# SCH_V1_0.net
KiCad netlist of a schematic drawn in Altium Designer
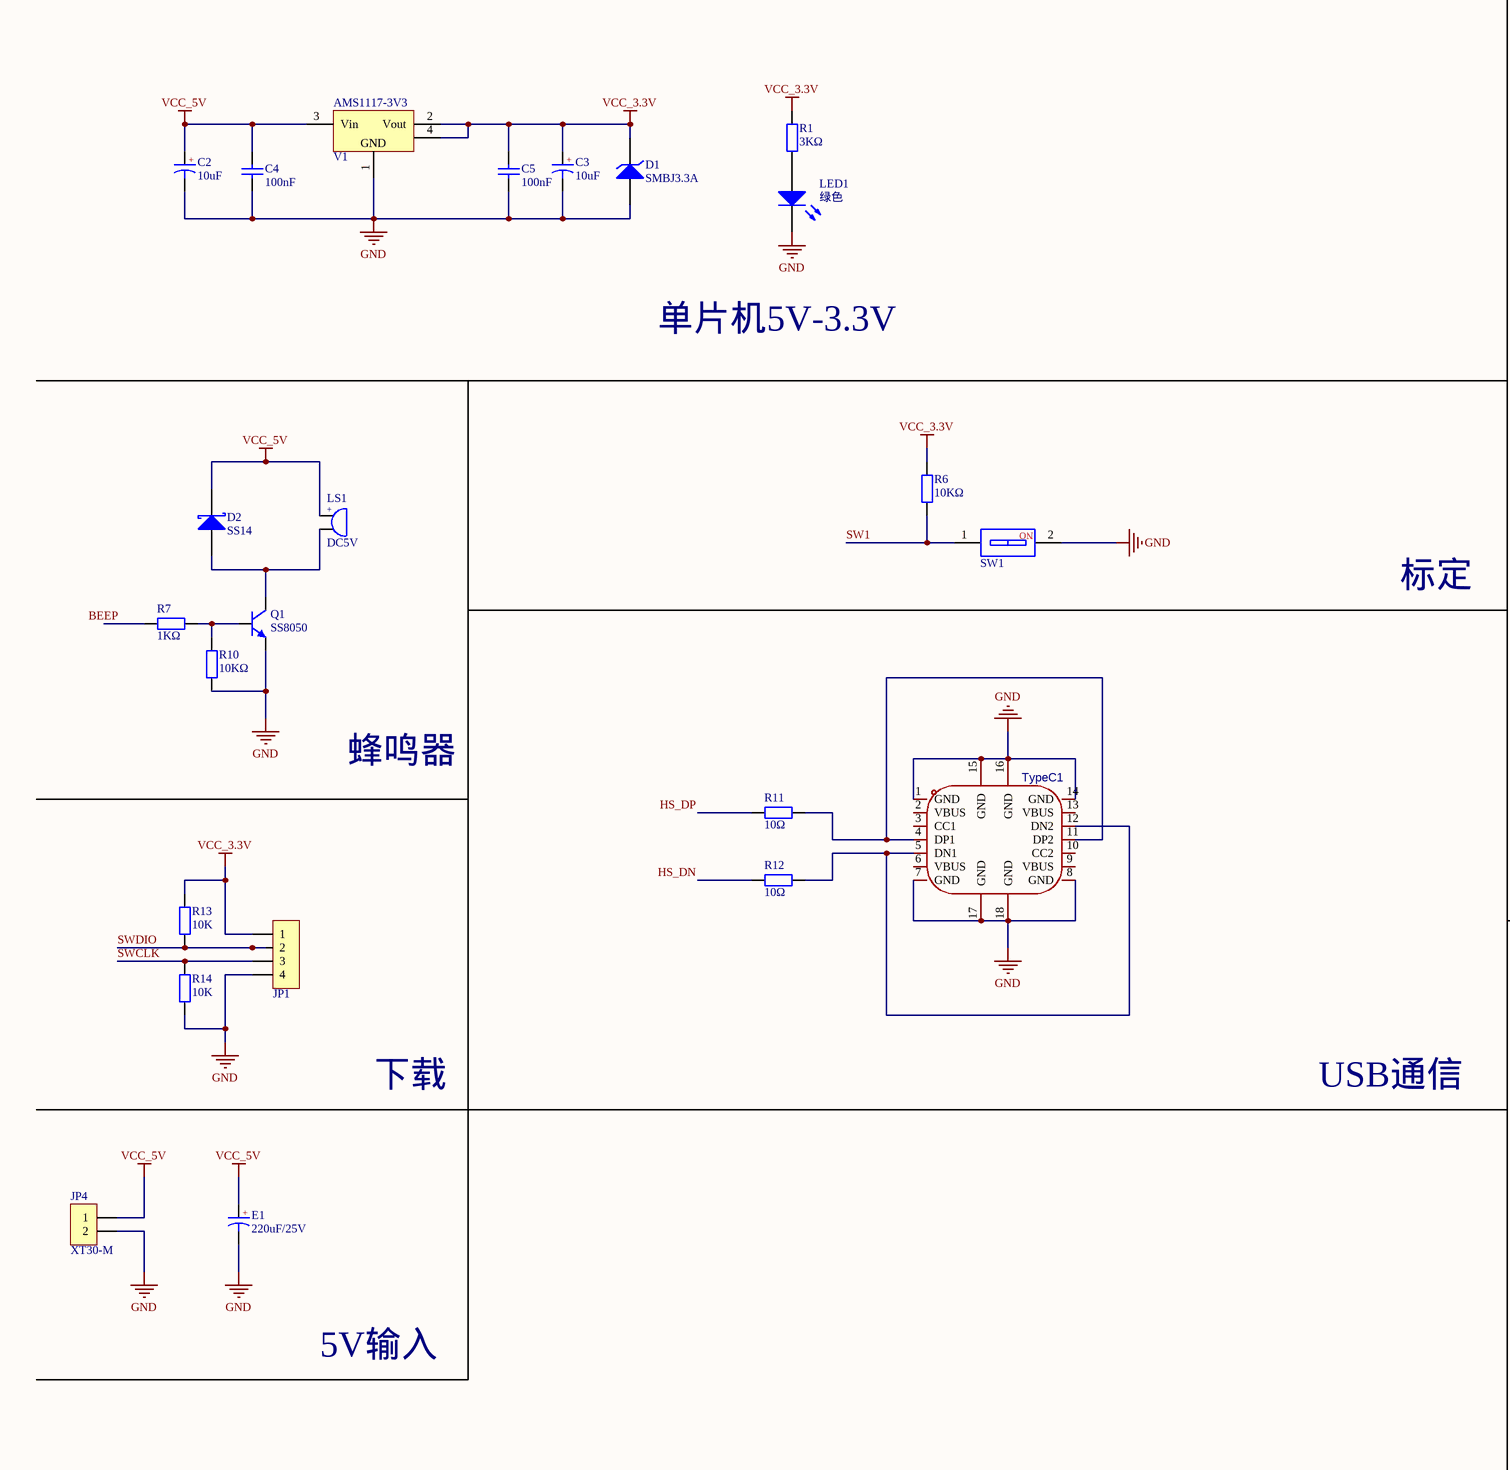
[diagram p0: SCH_V1.0.SchDoc, left]
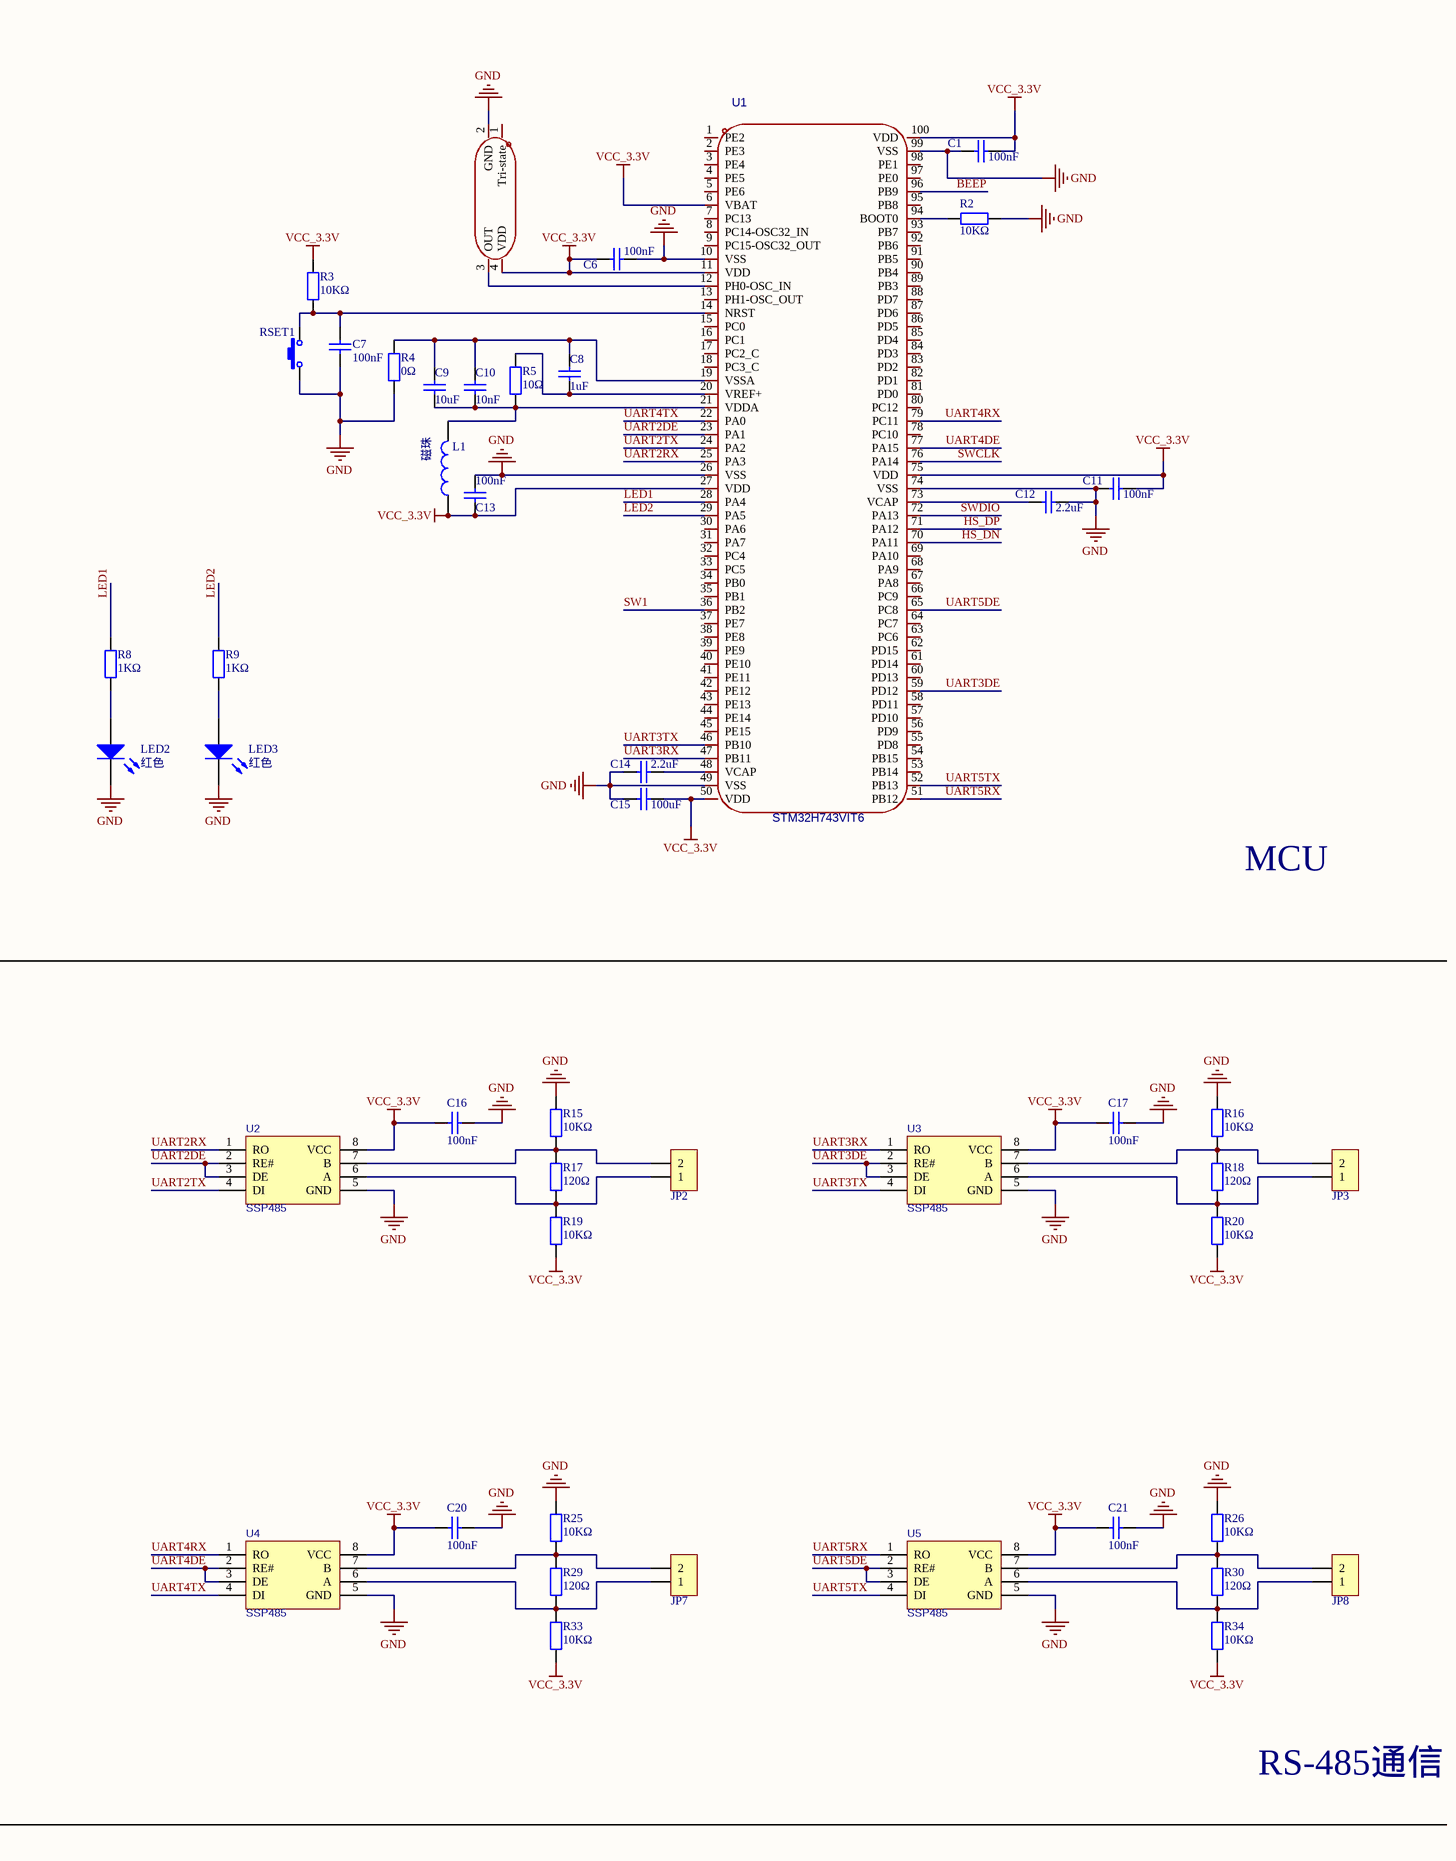
[diagram p1: SCH_V1.0.SchDoc, right]

(export (version "E")
  (design (tool "Eeschema 10.0.6"))
  (components
    (comp (ref "C1")
      (value "100nF")
      (footprint "C0603_L")
      (description "贴片电容/MLCC电容")
      (libsource (lib "0.1 - 电阻-电容-电感-保险丝-晶振-晶体-磁珠-电位器-法拉电容-馈通电容") (part "C"))
    )
    (comp (ref "C2")
      (value "10uF")
      (footprint "C_3216")
      (description "贴片钽电容")
      (libsource (lib "0.1 - 电阻-电容-电感-保险丝-晶振-晶体-磁珠-电位器-法拉电容-馈通电容") (part "CT"))
    )
    (comp (ref "C3")
      (value "10uF")
      (footprint "C_3216")
      (description "贴片钽电容")
      (libsource (lib "0.1 - 电阻-电容-电感-保险丝-晶振-晶体-磁珠-电位器-法拉电容-馈通电容") (part "CT"))
    )
    (comp (ref "C4")
      (value "100nF")
      (footprint "C1206_L")
      (description "贴片电容/MLCC电容")
      (libsource (lib "0.1 - 电阻-电容-电感-保险丝-晶振-晶体-磁珠-电位器-法拉电容-馈通电容") (part "C"))
    )
    (comp (ref "C5")
      (value "100nF")
      (footprint "C1206_L")
      (description "贴片电容/MLCC电容")
      (libsource (lib "0.1 - 电阻-电容-电感-保险丝-晶振-晶体-磁珠-电位器-法拉电容-馈通电容") (part "C"))
    )
    (comp (ref "C6")
      (value "100nF")
      (footprint "C0603_L")
      (description "贴片电容/MLCC电容")
      (libsource (lib "0.1 - 电阻-电容-电感-保险丝-晶振-晶体-磁珠-电位器-法拉电容-馈通电容") (part "C"))
    )
    (comp (ref "C7")
      (value "100nF")
      (footprint "C0603_L")
      (description "贴片电容/MLCC电容")
      (libsource (lib "0.1 - 电阻-电容-电感-保险丝-晶振-晶体-磁珠-电位器-法拉电容-馈通电容") (part "C"))
    )
    (comp (ref "C8")
      (value "1uF")
      (footprint "C0603_L")
      (description "贴片电容/MLCC电容")
      (libsource (lib "0.1 - 电阻-电容-电感-保险丝-晶振-晶体-磁珠-电位器-法拉电容-馈通电容") (part "C"))
    )
    (comp (ref "C9")
      (value "10uF")
      (footprint "C0603_L")
      (description "贴片电容/MLCC电容")
      (libsource (lib "0.1 - 电阻-电容-电感-保险丝-晶振-晶体-磁珠-电位器-法拉电容-馈通电容") (part "C"))
    )
    (comp (ref "C10")
      (value "10nF")
      (footprint "C0603_L")
      (description "贴片电容/MLCC电容")
      (libsource (lib "0.1 - 电阻-电容-电感-保险丝-晶振-晶体-磁珠-电位器-法拉电容-馈通电容") (part "C"))
    )
    (comp (ref "C11")
      (value "100nF")
      (footprint "C0603_L")
      (description "贴片电容/MLCC电容")
      (libsource (lib "0.1 - 电阻-电容-电感-保险丝-晶振-晶体-磁珠-电位器-法拉电容-馈通电容") (part "C"))
    )
    (comp (ref "C12")
      (value "2.2uF")
      (footprint "C0603_L")
      (description "贴片电容/MLCC电容")
      (libsource (lib "0.1 - 电阻-电容-电感-保险丝-晶振-晶体-磁珠-电位器-法拉电容-馈通电容") (part "C"))
    )
    (comp (ref "C13")
      (value "100nF")
      (footprint "C0603_L")
      (description "贴片电容/MLCC电容")
      (libsource (lib "0.1 - 电阻-电容-电感-保险丝-晶振-晶体-磁珠-电位器-法拉电容-馈通电容") (part "C"))
    )
    (comp (ref "C14")
      (value "2.2uF")
      (footprint "C0603_L")
      (description "贴片电容/MLCC电容")
      (libsource (lib "0.1 - 电阻-电容-电感-保险丝-晶振-晶体-磁珠-电位器-法拉电容-馈通电容") (part "C"))
    )
    (comp (ref "C15")
      (value "100uF")
      (footprint "C0603_L")
      (description "贴片电容/MLCC电容")
      (libsource (lib "0.1 - 电阻-电容-电感-保险丝-晶振-晶体-磁珠-电位器-法拉电容-馈通电容") (part "C"))
    )
    (comp (ref "C16")
      (value "100nF")
      (footprint "C0603_L")
      (description "瓷片电容")
      (libsource (lib "0.1 - 电阻-电容-电感-保险丝-晶振-晶体-磁珠-电位器-法拉电容-馈通电容") (part "CC"))
    )
    (comp (ref "C17")
      (value "100nF")
      (footprint "C0603_L")
      (description "瓷片电容")
      (libsource (lib "0.1 - 电阻-电容-电感-保险丝-晶振-晶体-磁珠-电位器-法拉电容-馈通电容") (part "CC"))
    )
    (comp (ref "C20")
      (value "100nF")
      (footprint "C0603_L")
      (description "瓷片电容")
      (libsource (lib "0.1 - 电阻-电容-电感-保险丝-晶振-晶体-磁珠-电位器-法拉电容-馈通电容") (part "CC"))
    )
    (comp (ref "C21")
      (value "100nF")
      (footprint "C0603_L")
      (description "瓷片电容")
      (libsource (lib "0.1 - 电阻-电容-电感-保险丝-晶振-晶体-磁珠-电位器-法拉电容-馈通电容") (part "CC"))
    )
    (comp (ref "D1")
      (value "SMBJ3.3A")
      (footprint "SMB")
      (description "30V 600W瞬态抑制二极管")
      (libsource (lib "0.2 - 二极管-TVS-ESD-整流桥-放电管") (part "SMBJ30A-E3/52"))
    )
    (comp (ref "D2")
      (value "SS14")
      (footprint "SMA")
      (description "肖特基二极管")
      (libsource (lib "0.2 - 二极管-TVS-ESD-整流桥-放电管") (part "SS14"))
    )
    (comp (ref "E1")
      (value "220uF/25V")
      (footprint "CS 6*6 - B")
      (description "贴片固态电容")
      (libsource (lib "0.1 - 电阻-电容-电感-保险丝-晶振-晶体-磁珠-电位器-法拉电容-馈通电容") (part "CS_SMD"))
    )
    (comp (ref "JP1")
      (value "HDR-1X4")
      (footprint "XH2.54-W-4P")
      (description "4P接插件")
      (libsource (lib "5.5 - 2.54mm连接器(KF2EDGK_XH2.54_2.54排针排母)") (part "Header 4"))
    )
    (comp (ref "JP2")
      (value "HDR-1X2")
      (footprint "XH2.54-W-2P")
      (description "2P接插件")
      (libsource (lib "5.5 - 2.54mm连接器(KF2EDGK_XH2.54_2.54排针排母)") (part "Header 2"))
    )
    (comp (ref "JP3")
      (value "HDR-1X2")
      (footprint "XH2.54-W-2P")
      (description "2P接插件")
      (libsource (lib "5.5 - 2.54mm连接器(KF2EDGK_XH2.54_2.54排针排母)") (part "Header 2"))
    )
    (comp (ref "JP4")
      (value "XT30-M")
      (footprint "XT30PW-M")
      (description "XT30公头")
      (libsource (lib "0.6 - 电源_音频_USB Type-C_HDMI_XT60_5557_D-SUB_RJ45_SD-TF_SIM插座") (part "XT30-M"))
    )
    (comp (ref "JP7")
      (value "HDR-1X2")
      (footprint "XH2.54-W-2P")
      (description "2P接插件")
      (libsource (lib "5.5 - 2.54mm连接器(KF2EDGK_XH2.54_2.54排针排母)") (part "Header 2"))
    )
    (comp (ref "JP8")
      (value "HDR-1X2")
      (footprint "XH2.54-W-2P")
      (description "2P接插件")
      (libsource (lib "5.5 - 2.54mm连接器(KF2EDGK_XH2.54_2.54排针排母)") (part "Header 2"))
    )
    (comp (ref "L1")
      (value "磁珠")
      (footprint "L0603")
      (description "贴片小功率电感")
      (libsource (lib "0.1 - 电阻-电容-电感-保险丝-晶振-晶体-磁珠-电位器-法拉电容-馈通电容") (part "L"))
    )
    (comp (ref "LED1")
      (value "绿色")
      (footprint "LED0603_B")
      (description "贴片LED")
      (libsource (lib "0.3 - LED发光二极管-IR二极管_接收管-光耦") (part "LED"))
    )
    (comp (ref "LED2")
      (value "红色")
      (footprint "LED0603_G")
      (description "贴片LED")
      (libsource (lib "0.3 - LED发光二极管-IR二极管_接收管-光耦") (part "LED"))
    )
    (comp (ref "LED3")
      (value "红色")
      (footprint "LED0603_R")
      (description "贴片LED")
      (libsource (lib "0.3 - LED发光二极管-IR二极管_接收管-光耦") (part "LED"))
    )
    (comp (ref "LS1")
      (value "DC5V")
      (footprint "BEEP 5x9x5.5")
      (description "蜂鸣器")
      (libsource (lib "0.5 - 按键_开关_蜂鸣器_电池_测试点_Mark点_铜柱") (part "BEEP"))
    )
    (comp (ref "OSC1")
      (value "8MHz")
      (footprint "XTAL-3225-4P")
      (fields
        (field (name "MANUFACTURER") "YXC(扬兴晶振)")
        (field (name "MANUFACTURER PART") "OT2EL4C4JI-111OLP-8M")
      )
      (libsource (lib "0.1 - 电阻-电容-电感-保险丝-晶振-晶体-磁珠-电位器-法拉电容-馈通电容") (part "XTAL-OT2EL4C4JI"))
    )
    (comp (ref "Q1")
      (value "SS8050")
      (footprint "SOT23-3N")
      (description "高频放大-NPN型")
      (libsource (lib "0.4 - 三极管-场效应管-可控硅") (part "8050-SMD"))
    )
    (comp (ref "R1")
      (value "3KΩ")
      (footprint "R0603_L")
      (description "贴片电阻")
      (libsource (lib "0.1 - 电阻-电容-电感-保险丝-晶振-晶体-磁珠-电位器-法拉电容-馈通电容") (part "R"))
    )
    (comp (ref "R2")
      (value "10KΩ")
      (footprint "R0603_L")
      (description "贴片电阻")
      (libsource (lib "0.1 - 电阻-电容-电感-保险丝-晶振-晶体-磁珠-电位器-法拉电容-馈通电容") (part "R"))
    )
    (comp (ref "R3")
      (value "10KΩ")
      (footprint "R0603_L")
      (description "贴片电阻")
      (libsource (lib "0.1 - 电阻-电容-电感-保险丝-晶振-晶体-磁珠-电位器-法拉电容-馈通电容") (part "R"))
    )
    (comp (ref "R4")
      (value "0Ω")
      (footprint "R0603_L")
      (description "贴片电阻")
      (libsource (lib "0.1 - 电阻-电容-电感-保险丝-晶振-晶体-磁珠-电位器-法拉电容-馈通电容") (part "R"))
    )
    (comp (ref "R5")
      (value "10Ω")
      (footprint "R0603_L")
      (description "贴片电阻")
      (libsource (lib "0.1 - 电阻-电容-电感-保险丝-晶振-晶体-磁珠-电位器-法拉电容-馈通电容") (part "R"))
    )
    (comp (ref "R6")
      (value "10KΩ")
      (footprint "R0603_L")
      (description "贴片电阻")
      (libsource (lib "0.1 - 电阻-电容-电感-保险丝-晶振-晶体-磁珠-电位器-法拉电容-馈通电容") (part "R"))
    )
    (comp (ref "R7")
      (value "1KΩ")
      (footprint "R0603_L")
      (description "贴片电阻")
      (libsource (lib "0.1 - 电阻-电容-电感-保险丝-晶振-晶体-磁珠-电位器-法拉电容-馈通电容") (part "R"))
    )
    (comp (ref "R8")
      (value "1KΩ")
      (footprint "R0603_L")
      (description "贴片电阻")
      (libsource (lib "0.1 - 电阻-电容-电感-保险丝-晶振-晶体-磁珠-电位器-法拉电容-馈通电容") (part "R"))
    )
    (comp (ref "R9")
      (value "1KΩ")
      (footprint "R0603_L")
      (description "贴片电阻")
      (libsource (lib "0.1 - 电阻-电容-电感-保险丝-晶振-晶体-磁珠-电位器-法拉电容-馈通电容") (part "R"))
    )
    (comp (ref "R10")
      (value "10KΩ")
      (footprint "R0603_L")
      (description "贴片电阻")
      (libsource (lib "0.1 - 电阻-电容-电感-保险丝-晶振-晶体-磁珠-电位器-法拉电容-馈通电容") (part "R"))
    )
    (comp (ref "R11")
      (value "10Ω")
      (footprint "R0603_L")
      (description "贴片电阻")
      (libsource (lib "0.1 - 电阻-电容-电感-保险丝-晶振-晶体-磁珠-电位器-法拉电容-馈通电容") (part "R"))
    )
    (comp (ref "R12")
      (value "10Ω")
      (footprint "R0603_L")
      (description "贴片电阻")
      (libsource (lib "0.1 - 电阻-电容-电感-保险丝-晶振-晶体-磁珠-电位器-法拉电容-馈通电容") (part "R"))
    )
    (comp (ref "R13")
      (value "10K")
      (footprint "R0603_L")
      (description "贴片电阻")
      (libsource (lib "0.1 - 电阻-电容-电感-保险丝-晶振-晶体-磁珠-电位器-法拉电容-馈通电容") (part "R"))
    )
    (comp (ref "R14")
      (value "10K")
      (footprint "R0603_L")
      (description "贴片电阻")
      (libsource (lib "0.1 - 电阻-电容-电感-保险丝-晶振-晶体-磁珠-电位器-法拉电容-馈通电容") (part "R"))
    )
    (comp (ref "R15")
      (value "10KΩ")
      (footprint "R0603_L")
      (description "贴片电阻")
      (libsource (lib "0.1 - 电阻-电容-电感-保险丝-晶振-晶体-磁珠-电位器-法拉电容-馈通电容") (part "R"))
    )
    (comp (ref "R16")
      (value "10KΩ")
      (footprint "R0603_L")
      (description "贴片电阻")
      (libsource (lib "0.1 - 电阻-电容-电感-保险丝-晶振-晶体-磁珠-电位器-法拉电容-馈通电容") (part "R"))
    )
    (comp (ref "R17")
      (value "120Ω")
      (footprint "R0603_L")
      (description "贴片电阻")
      (libsource (lib "0.1 - 电阻-电容-电感-保险丝-晶振-晶体-磁珠-电位器-法拉电容-馈通电容") (part "R"))
    )
    (comp (ref "R18")
      (value "120Ω")
      (footprint "R0603_L")
      (description "贴片电阻")
      (libsource (lib "0.1 - 电阻-电容-电感-保险丝-晶振-晶体-磁珠-电位器-法拉电容-馈通电容") (part "R"))
    )
    (comp (ref "R19")
      (value "10KΩ")
      (footprint "R0603_L")
      (description "贴片电阻")
      (libsource (lib "0.1 - 电阻-电容-电感-保险丝-晶振-晶体-磁珠-电位器-法拉电容-馈通电容") (part "R"))
    )
    (comp (ref "R20")
      (value "10KΩ")
      (footprint "R0603_L")
      (description "贴片电阻")
      (libsource (lib "0.1 - 电阻-电容-电感-保险丝-晶振-晶体-磁珠-电位器-法拉电容-馈通电容") (part "R"))
    )
    (comp (ref "R25")
      (value "10KΩ")
      (footprint "R0603_L")
      (description "贴片电阻")
      (libsource (lib "0.1 - 电阻-电容-电感-保险丝-晶振-晶体-磁珠-电位器-法拉电容-馈通电容") (part "R"))
    )
    (comp (ref "R26")
      (value "10KΩ")
      (footprint "R0603_L")
      (description "贴片电阻")
      (libsource (lib "0.1 - 电阻-电容-电感-保险丝-晶振-晶体-磁珠-电位器-法拉电容-馈通电容") (part "R"))
    )
    (comp (ref "R29")
      (value "120Ω")
      (footprint "R0603_L")
      (description "贴片电阻")
      (libsource (lib "0.1 - 电阻-电容-电感-保险丝-晶振-晶体-磁珠-电位器-法拉电容-馈通电容") (part "R"))
    )
    (comp (ref "R30")
      (value "120Ω")
      (footprint "R0603_L")
      (description "贴片电阻")
      (libsource (lib "0.1 - 电阻-电容-电感-保险丝-晶振-晶体-磁珠-电位器-法拉电容-馈通电容") (part "R"))
    )
    (comp (ref "R33")
      (value "10KΩ")
      (footprint "R0603_L")
      (description "贴片电阻")
      (libsource (lib "0.1 - 电阻-电容-电感-保险丝-晶振-晶体-磁珠-电位器-法拉电容-馈通电容") (part "R"))
    )
    (comp (ref "R34")
      (value "10KΩ")
      (footprint "R0603_L")
      (description "贴片电阻")
      (libsource (lib "0.1 - 电阻-电容-电感-保险丝-晶振-晶体-磁珠-电位器-法拉电容-馈通电容") (part "R"))
    )
    (comp (ref "RSET1")
      (value "3x6x5")
      (footprint "SW SMD-3*6*2.5")
      (description "微动开关")
      (libsource (lib "0.5 - 按键_开关_蜂鸣器_电池_测试点_Mark点_铜柱") (part "SW-PB"))
    )
    (comp (ref "SW1")
      (value "DIP-SW-1P")
      (footprint "SW DIP-1P")
      (description "1路拨码开关")
      (libsource (lib "0.5 - 按键_开关_蜂鸣器_电池_测试点_Mark点_铜柱") (part "DIP-SW-1P"))
    )
    (comp (ref "TypeC1")
      (value "U264-141N-4BAC10")
      (footprint "USB-C-Type-侧插")
      (fields (field (name "MANUFACTURER") "XKB Connectivity(中国星坤)"))
      (libsource (lib "0.6 - 电源_音频_USB Type-C_HDMI_XT60_5557_D-SUB_RJ45_SD-TF_SIM插座") (part "USB3.0-Type-C-侧插"))
    )
    (comp (ref "U1")
      (value "STM32H743VIT6")
      (footprint "LQFP-100_L14.0-W14.0-P0.50-LS16.0-BL")
      (fields (field (name "MANUFACTURER") "ST(意法半导体)"))
      (libsource (lib "2.8 - STM32 F7-H7-MP系列单片机") (part "STM32H743VIT6_C114409"))
    )
    (comp (ref "U2")
      (value "SSP485")
      (footprint "SOP-8")
      (description "RS485/RS422收发器芯片")
      (libsource (lib "0.8 - 常见芯片") (part "MAX3485CSA"))
    )
    (comp (ref "U3")
      (value "SSP485")
      (footprint "SOP-8")
      (description "RS485/RS422收发器芯片")
      (libsource (lib "0.8 - 常见芯片") (part "MAX3485CSA"))
    )
    (comp (ref "U4")
      (value "SSP485")
      (footprint "SOP-8")
      (description "RS485/RS422收发器芯片")
      (libsource (lib "0.8 - 常见芯片") (part "MAX3485CSA"))
    )
    (comp (ref "U5")
      (value "SSP485")
      (footprint "SOP-8")
      (description "RS485/RS422收发器芯片")
      (libsource (lib "0.8 - 常见芯片") (part "MAX3485CSA"))
    )
    (comp (ref "V1")
      (value "AMS1117-3V3")
      (footprint "SOT223_L")
      (description "三端稳压芯片")
      (libsource (lib "0.7 - 电源类芯片") (part "AMS1117"))
    )
  )
  (nets
    (net (code "1") (name "/BEEP") (class "Default")
      (node (ref "R7") (pin "1") (pinfunction "1_1") (pintype "passive"))
      (node (ref "U1") (pin "96") (pinfunction "PB9_96") (pintype "passive"))
    )
    (net (code "2") (name "/HS_DN") (class "Default")
      (node (ref "R12") (pin "1") (pinfunction "1_1") (pintype "passive"))
      (node (ref "U1") (pin "70") (pinfunction "PA11_70") (pintype "passive"))
    )
    (net (code "3") (name "/HS_DP") (class "Default")
      (node (ref "R11") (pin "1") (pinfunction "1_1") (pintype "passive"))
      (node (ref "U1") (pin "71") (pinfunction "PA12_71") (pintype "passive"))
    )
    (net (code "4") (name "/LED1") (class "Default")
      (node (ref "R8") (pin "2") (pinfunction "2_2") (pintype "passive"))
      (node (ref "U1") (pin "28") (pinfunction "PA4_28") (pintype "passive"))
    )
    (net (code "5") (name "/LED2") (class "Default")
      (node (ref "R9") (pin "2") (pinfunction "2_2") (pintype "passive"))
      (node (ref "U1") (pin "29") (pinfunction "PA5_29") (pintype "passive"))
    )
    (net (code "6") (name "/SW1") (class "Default")
      (node (ref "R6") (pin "1") (pinfunction "1_1") (pintype "passive"))
      (node (ref "SW1") (pin "1") (pinfunction "1_1") (pintype "passive"))
      (node (ref "U1") (pin "36") (pinfunction "PB2_36") (pintype "passive"))
    )
    (net (code "7") (name "/SWCLK") (class "Default")
      (node (ref "JP1") (pin "3") (pinfunction "3_3") (pintype "passive"))
      (node (ref "R14") (pin "2") (pinfunction "2_2") (pintype "passive"))
      (node (ref "U1") (pin "76") (pinfunction "PA14_76") (pintype "passive"))
    )
    (net (code "8") (name "/SWDIO") (class "Default")
      (node (ref "JP1") (pin "2") (pinfunction "2_2") (pintype "passive"))
      (node (ref "R13") (pin "1") (pinfunction "1_1") (pintype "passive"))
      (node (ref "U1") (pin "72") (pinfunction "PA13_72") (pintype "passive"))
    )
    (net (code "9") (name "/UART2DE") (class "Default")
      (node (ref "U1") (pin "23") (pinfunction "PA1_23") (pintype "passive"))
      (node (ref "U2") (pin "2") (pinfunction "RE#_2") (pintype "passive"))
      (node (ref "U2") (pin "3") (pinfunction "DE_3") (pintype "passive"))
    )
    (net (code "10") (name "/UART2RX") (class "Default")
      (node (ref "U1") (pin "25") (pinfunction "PA3_25") (pintype "passive"))
      (node (ref "U2") (pin "1") (pinfunction "RO_1") (pintype "passive"))
    )
    (net (code "11") (name "/UART2TX") (class "Default")
      (node (ref "U1") (pin "24") (pinfunction "PA2_24") (pintype "passive"))
      (node (ref "U2") (pin "4") (pinfunction "DI_4") (pintype "passive"))
    )
    (net (code "12") (name "/UART3DE") (class "Default")
      (node (ref "U1") (pin "59") (pinfunction "PD12_59") (pintype "passive"))
      (node (ref "U3") (pin "2") (pinfunction "RE#_2") (pintype "passive"))
      (node (ref "U3") (pin "3") (pinfunction "DE_3") (pintype "passive"))
    )
    (net (code "13") (name "/UART3RX") (class "Default")
      (node (ref "U1") (pin "47") (pinfunction "PB11_47") (pintype "passive"))
      (node (ref "U3") (pin "1") (pinfunction "RO_1") (pintype "passive"))
    )
    (net (code "14") (name "/UART3TX") (class "Default")
      (node (ref "U1") (pin "46") (pinfunction "PB10_46") (pintype "passive"))
      (node (ref "U3") (pin "4") (pinfunction "DI_4") (pintype "passive"))
    )
    (net (code "15") (name "/UART4DE") (class "Default")
      (node (ref "U1") (pin "77") (pinfunction "PA15_77") (pintype "passive"))
      (node (ref "U4") (pin "2") (pinfunction "RE#_2") (pintype "passive"))
      (node (ref "U4") (pin "3") (pinfunction "DE_3") (pintype "passive"))
    )
    (net (code "16") (name "/UART4RX") (class "Default")
      (node (ref "U1") (pin "79") (pinfunction "PC11_79") (pintype "passive"))
      (node (ref "U4") (pin "1") (pinfunction "RO_1") (pintype "passive"))
    )
    (net (code "17") (name "/UART4TX") (class "Default")
      (node (ref "U1") (pin "22") (pinfunction "PA0_22") (pintype "passive"))
      (node (ref "U4") (pin "4") (pinfunction "DI_4") (pintype "passive"))
    )
    (net (code "18") (name "/UART5DE") (class "Default")
      (node (ref "U1") (pin "65") (pinfunction "PC8_65") (pintype "passive"))
      (node (ref "U5") (pin "2") (pinfunction "RE#_2") (pintype "passive"))
      (node (ref "U5") (pin "3") (pinfunction "DE_3") (pintype "passive"))
    )
    (net (code "19") (name "/UART5RX") (class "Default")
      (node (ref "U1") (pin "51") (pinfunction "PB12_51") (pintype "passive"))
      (node (ref "U5") (pin "1") (pinfunction "RO_1") (pintype "passive"))
    )
    (net (code "20") (name "/UART5TX") (class "Default")
      (node (ref "U1") (pin "52") (pinfunction "PB13_52") (pintype "passive"))
      (node (ref "U5") (pin "4") (pinfunction "DI_4") (pintype "passive"))
    )
    (net (code "21") (name "GND") (class "Default")
      (node (ref "C1") (pin "1") (pinfunction "1_1") (pintype "passive"))
      (node (ref "C11") (pin "1") (pinfunction "1_1") (pintype "passive"))
      (node (ref "C12") (pin "2") (pinfunction "2_2") (pintype "passive"))
      (node (ref "C13") (pin "1") (pinfunction "1_1") (pintype "passive"))
      (node (ref "C14") (pin "1") (pinfunction "1_1") (pintype "passive"))
      (node (ref "C15") (pin "1") (pinfunction "1_1") (pintype "passive"))
      (node (ref "C16") (pin "2") (pinfunction "2_2") (pintype "passive"))
      (node (ref "C17") (pin "2") (pinfunction "2_2") (pintype "passive"))
      (node (ref "C2") (pin "2") (pinfunction "K_2") (pintype "passive"))
      (node (ref "C20") (pin "2") (pinfunction "2_2") (pintype "passive"))
      (node (ref "C21") (pin "2") (pinfunction "2_2") (pintype "passive"))
      (node (ref "C3") (pin "2") (pinfunction "K_2") (pintype "passive"))
      (node (ref "C4") (pin "1") (pinfunction "1_1") (pintype "passive"))
      (node (ref "C5") (pin "1") (pinfunction "1_1") (pintype "passive"))
      (node (ref "C6") (pin "2") (pinfunction "2_2") (pintype "passive"))
      (node (ref "C7") (pin "1") (pinfunction "1_1") (pintype "passive"))
      (node (ref "D1") (pin "1") (pinfunction "A_1") (pintype "passive"))
      (node (ref "E1") (pin "2") (pinfunction "2_2") (pintype "passive"))
      (node (ref "JP1") (pin "4") (pinfunction "4_4") (pintype "passive"))
      (node (ref "JP4") (pin "2") (pinfunction "2_2") (pintype "passive"))
      (node (ref "LED1") (pin "2") (pinfunction "K_2") (pintype "passive"))
      (node (ref "LED2") (pin "2") (pinfunction "K_2") (pintype "passive"))
      (node (ref "LED3") (pin "2") (pinfunction "K_2") (pintype "passive"))
      (node (ref "OSC1") (pin "2") (pinfunction "GND_2") (pintype "passive"))
      (node (ref "Q1") (pin "2") (pinfunction "E_2") (pintype "passive"))
      (node (ref "R10") (pin "2") (pinfunction "2_2") (pintype "passive"))
      (node (ref "R14") (pin "1") (pinfunction "1_1") (pintype "passive"))
      (node (ref "R15") (pin "2") (pinfunction "2_2") (pintype "passive"))
      (node (ref "R16") (pin "2") (pinfunction "2_2") (pintype "passive"))
      (node (ref "R2") (pin "2") (pinfunction "2_2") (pintype "passive"))
      (node (ref "R25") (pin "2") (pinfunction "2_2") (pintype "passive"))
      (node (ref "R26") (pin "2") (pinfunction "2_2") (pintype "passive"))
      (node (ref "R4") (pin "1") (pinfunction "1_1") (pintype "passive"))
      (node (ref "RSET1") (pin "1") (pinfunction "1_1") (pintype "passive"))
      (node (ref "SW1") (pin "2") (pinfunction "2_2") (pintype "passive"))
      (node (ref "TypeC1") (pin "1") (pinfunction "GND_1") (pintype "passive"))
      (node (ref "TypeC1") (pin "14") (pinfunction "GND_14") (pintype "passive"))
      (node (ref "TypeC1") (pin "15") (pinfunction "GND_15") (pintype "passive"))
      (node (ref "TypeC1") (pin "16") (pinfunction "GND_16") (pintype "passive"))
      (node (ref "TypeC1") (pin "17") (pinfunction "GND_17") (pintype "passive"))
      (node (ref "TypeC1") (pin "18") (pinfunction "GND_18") (pintype "passive"))
      (node (ref "TypeC1") (pin "7") (pinfunction "GND_7") (pintype "passive"))
      (node (ref "TypeC1") (pin "8") (pinfunction "GND_8") (pintype "passive"))
      (node (ref "U1") (pin "10") (pinfunction "VSS_10") (pintype "passive"))
      (node (ref "U1") (pin "26") (pinfunction "VSS_26") (pintype "passive"))
      (node (ref "U1") (pin "49") (pinfunction "VSS_49") (pintype "passive"))
      (node (ref "U1") (pin "74") (pinfunction "VSS_74") (pintype "passive"))
      (node (ref "U1") (pin "99") (pinfunction "VSS_99") (pintype "passive"))
      (node (ref "U2") (pin "5") (pinfunction "GND_5") (pintype "passive"))
      (node (ref "U3") (pin "5") (pinfunction "GND_5") (pintype "passive"))
      (node (ref "U4") (pin "5") (pinfunction "GND_5") (pintype "passive"))
      (node (ref "U5") (pin "5") (pinfunction "GND_5") (pintype "passive"))
      (node (ref "V1") (pin "1") (pinfunction "GND_1") (pintype "passive"))
    )
    (net (code "22") (name "Net-(C12-Pad1)") (class "Default")
      (node (ref "C12") (pin "1") (pinfunction "1_1") (pintype "passive"))
      (node (ref "U1") (pin "73") (pinfunction "VCAP_73") (pintype "passive"))
    )
    (net (code "23") (name "Net-(C14-Pad2)") (class "Default")
      (node (ref "C14") (pin "2") (pinfunction "2_2") (pintype "passive"))
      (node (ref "U1") (pin "48") (pinfunction "VCAP_48") (pintype "passive"))
    )
    (net (code "24") (name "Net-(D2-A)") (class "Default")
      (node (ref "D2") (pin "1") (pinfunction "A_1") (pintype "passive"))
      (node (ref "LS1") (pin "2") (pinfunction "2_2") (pintype "passive"))
      (node (ref "Q1") (pin "3") (pinfunction "C_3") (pintype "passive"))
    )
    (net (code "25") (name "Net-(LED1-A)") (class "Default")
      (node (ref "LED1") (pin "1") (pinfunction "A_1") (pintype "passive"))
      (node (ref "R1") (pin "2") (pinfunction "2_2") (pintype "passive"))
    )
    (net (code "26") (name "Net-(LED2-A)") (class "Default")
      (node (ref "LED2") (pin "1") (pinfunction "A_1") (pintype "passive"))
      (node (ref "R8") (pin "1") (pinfunction "1_1") (pintype "passive"))
    )
    (net (code "27") (name "Net-(LED3-A)") (class "Default")
      (node (ref "LED3") (pin "1") (pinfunction "A_1") (pintype "passive"))
      (node (ref "R9") (pin "1") (pinfunction "1_1") (pintype "passive"))
    )
    (net (code "28") (name "Net-(OSC1-OUT)") (class "Default")
      (node (ref "OSC1") (pin "3") (pinfunction "OUT_3") (pintype "passive"))
      (node (ref "U1") (pin "12") (pinfunction "PH0-OSC_IN_12") (pintype "passive"))
    )
    (net (code "29") (name "Net-(Q1-B)") (class "Default")
      (node (ref "Q1") (pin "1") (pinfunction "B_1") (pintype "passive"))
      (node (ref "R10") (pin "1") (pinfunction "1_1") (pintype "passive"))
      (node (ref "R7") (pin "2") (pinfunction "2_2") (pintype "passive"))
    )
    (net (code "30") (name "Net-(TypeC1-DN1)") (class "Default")
      (node (ref "R12") (pin "2") (pinfunction "2_2") (pintype "passive"))
      (node (ref "TypeC1") (pin "12") (pinfunction "DN2_12") (pintype "passive"))
      (node (ref "TypeC1") (pin "5") (pinfunction "DN1_5") (pintype "passive"))
    )
    (net (code "31") (name "Net-(TypeC1-DP1)") (class "Default")
      (node (ref "R11") (pin "2") (pinfunction "2_2") (pintype "passive"))
      (node (ref "TypeC1") (pin "11") (pinfunction "DP2_11") (pintype "passive"))
      (node (ref "TypeC1") (pin "4") (pinfunction "DP1_4") (pintype "passive"))
    )
    (net (code "32") (name "Net-(U1-BOOT0)") (class "Default")
      (node (ref "R2") (pin "1") (pinfunction "1_1") (pintype "passive"))
      (node (ref "U1") (pin "94") (pinfunction "BOOT0_94") (pintype "passive"))
    )
    (net (code "33") (name "Net-(U1-NRST)") (class "Default")
      (node (ref "C7") (pin "2") (pinfunction "2_2") (pintype "passive"))
      (node (ref "R3") (pin "1") (pinfunction "1_1") (pintype "passive"))
      (node (ref "RSET1") (pin "2") (pinfunction "2_2") (pintype "passive"))
      (node (ref "U1") (pin "14") (pinfunction "NRST_14") (pintype "passive"))
    )
    (net (code "34") (name "Net-(U1-VDDA)") (class "Default")
      (node (ref "C10") (pin "1") (pinfunction "1_1") (pintype "passive"))
      (node (ref "C9") (pin "2") (pinfunction "2_2") (pintype "passive"))
      (node (ref "L1") (pin "2") (pinfunction "2_2") (pintype "passive"))
      (node (ref "R5") (pin "1") (pinfunction "1_1") (pintype "passive"))
      (node (ref "U1") (pin "21") (pinfunction "VDDA_21") (pintype "passive"))
    )
    (net (code "35") (name "Net-(U1-VREF+)") (class "Default")
      (node (ref "C8") (pin "1") (pinfunction "1_1") (pintype "passive"))
      (node (ref "R5") (pin "2") (pinfunction "2_2") (pintype "passive"))
      (node (ref "U1") (pin "20") (pinfunction "VREF+_20") (pintype "passive"))
    )
    (net (code "36") (name "Net-(U1-VSSA)") (class "Default")
      (node (ref "C10") (pin "2") (pinfunction "2_2") (pintype "passive"))
      (node (ref "C8") (pin "2") (pinfunction "2_2") (pintype "passive"))
      (node (ref "C9") (pin "1") (pinfunction "1_1") (pintype "passive"))
      (node (ref "R4") (pin "2") (pinfunction "2_2") (pintype "passive"))
      (node (ref "U1") (pin "19") (pinfunction "VSSA_19") (pintype "passive"))
    )
    (net (code "37") (name "Net-(U2-A)") (class "Default")
      (node (ref "JP2") (pin "1") (pinfunction "1_1") (pintype "passive"))
      (node (ref "R17") (pin "1") (pinfunction "1_1") (pintype "passive"))
      (node (ref "R19") (pin "2") (pinfunction "2_2") (pintype "passive"))
      (node (ref "U2") (pin "6") (pinfunction "A_6") (pintype "passive"))
    )
    (net (code "38") (name "Net-(U2-B)") (class "Default")
      (node (ref "JP2") (pin "2") (pinfunction "2_2") (pintype "passive"))
      (node (ref "R15") (pin "1") (pinfunction "1_1") (pintype "passive"))
      (node (ref "R17") (pin "2") (pinfunction "2_2") (pintype "passive"))
      (node (ref "U2") (pin "7") (pinfunction "B_7") (pintype "passive"))
    )
    (net (code "39") (name "Net-(U3-A)") (class "Default")
      (node (ref "JP3") (pin "1") (pinfunction "1_1") (pintype "passive"))
      (node (ref "R18") (pin "1") (pinfunction "1_1") (pintype "passive"))
      (node (ref "R20") (pin "2") (pinfunction "2_2") (pintype "passive"))
      (node (ref "U3") (pin "6") (pinfunction "A_6") (pintype "passive"))
    )
    (net (code "40") (name "Net-(U3-B)") (class "Default")
      (node (ref "JP3") (pin "2") (pinfunction "2_2") (pintype "passive"))
      (node (ref "R16") (pin "1") (pinfunction "1_1") (pintype "passive"))
      (node (ref "R18") (pin "2") (pinfunction "2_2") (pintype "passive"))
      (node (ref "U3") (pin "7") (pinfunction "B_7") (pintype "passive"))
    )
    (net (code "41") (name "Net-(U4-A)") (class "Default")
      (node (ref "JP7") (pin "1") (pinfunction "1_1") (pintype "passive"))
      (node (ref "R29") (pin "1") (pinfunction "1_1") (pintype "passive"))
      (node (ref "R33") (pin "2") (pinfunction "2_2") (pintype "passive"))
      (node (ref "U4") (pin "6") (pinfunction "A_6") (pintype "passive"))
    )
    (net (code "42") (name "Net-(U4-B)") (class "Default")
      (node (ref "JP7") (pin "2") (pinfunction "2_2") (pintype "passive"))
      (node (ref "R25") (pin "1") (pinfunction "1_1") (pintype "passive"))
      (node (ref "R29") (pin "2") (pinfunction "2_2") (pintype "passive"))
      (node (ref "U4") (pin "7") (pinfunction "B_7") (pintype "passive"))
    )
    (net (code "43") (name "Net-(U5-A)") (class "Default")
      (node (ref "JP8") (pin "1") (pinfunction "1_1") (pintype "passive"))
      (node (ref "R30") (pin "1") (pinfunction "1_1") (pintype "passive"))
      (node (ref "R34") (pin "2") (pinfunction "2_2") (pintype "passive"))
      (node (ref "U5") (pin "6") (pinfunction "A_6") (pintype "passive"))
    )
    (net (code "44") (name "Net-(U5-B)") (class "Default")
      (node (ref "JP8") (pin "2") (pinfunction "2_2") (pintype "passive"))
      (node (ref "R26") (pin "1") (pinfunction "1_1") (pintype "passive"))
      (node (ref "R30") (pin "2") (pinfunction "2_2") (pintype "passive"))
      (node (ref "U5") (pin "7") (pinfunction "B_7") (pintype "passive"))
    )
    (net (code "45") (name "VCC_3.3V") (class "Default")
      (node (ref "C1") (pin "2") (pinfunction "2_2") (pintype "passive"))
      (node (ref "C11") (pin "2") (pinfunction "2_2") (pintype "passive"))
      (node (ref "C13") (pin "2") (pinfunction "2_2") (pintype "passive"))
      (node (ref "C15") (pin "2") (pinfunction "2_2") (pintype "passive"))
      (node (ref "C16") (pin "1") (pinfunction "1_1") (pintype "passive"))
      (node (ref "C17") (pin "1") (pinfunction "1_1") (pintype "passive"))
      (node (ref "C20") (pin "1") (pinfunction "1_1") (pintype "passive"))
      (node (ref "C21") (pin "1") (pinfunction "1_1") (pintype "passive"))
      (node (ref "C3") (pin "1") (pinfunction "A_1") (pintype "passive"))
      (node (ref "C5") (pin "2") (pinfunction "2_2") (pintype "passive"))
      (node (ref "C6") (pin "1") (pinfunction "1_1") (pintype "passive"))
      (node (ref "D1") (pin "2") (pinfunction "K_2") (pintype "passive"))
      (node (ref "JP1") (pin "1") (pinfunction "1_1") (pintype "passive"))
      (node (ref "L1") (pin "1") (pinfunction "1_1") (pintype "passive"))
      (node (ref "OSC1") (pin "4") (pinfunction "VDD_4") (pintype "passive"))
      (node (ref "R1") (pin "1") (pinfunction "1_1") (pintype "passive"))
      (node (ref "R13") (pin "2") (pinfunction "2_2") (pintype "passive"))
      (node (ref "R19") (pin "1") (pinfunction "1_1") (pintype "passive"))
      (node (ref "R20") (pin "1") (pinfunction "1_1") (pintype "passive"))
      (node (ref "R3") (pin "2") (pinfunction "2_2") (pintype "passive"))
      (node (ref "R33") (pin "1") (pinfunction "1_1") (pintype "passive"))
      (node (ref "R34") (pin "1") (pinfunction "1_1") (pintype "passive"))
      (node (ref "R6") (pin "2") (pinfunction "2_2") (pintype "passive"))
      (node (ref "U1") (pin "100") (pinfunction "VDD_100") (pintype "passive"))
      (node (ref "U1") (pin "11") (pinfunction "VDD_11") (pintype "passive"))
      (node (ref "U1") (pin "27") (pinfunction "VDD_27") (pintype "passive"))
      (node (ref "U1") (pin "50") (pinfunction "VDD_50") (pintype "passive"))
      (node (ref "U1") (pin "6") (pinfunction "VBAT_6") (pintype "passive"))
      (node (ref "U1") (pin "75") (pinfunction "VDD_75") (pintype "passive"))
      (node (ref "U2") (pin "8") (pinfunction "VCC_8") (pintype "passive"))
      (node (ref "U3") (pin "8") (pinfunction "VCC_8") (pintype "passive"))
      (node (ref "U4") (pin "8") (pinfunction "VCC_8") (pintype "passive"))
      (node (ref "U5") (pin "8") (pinfunction "VCC_8") (pintype "passive"))
      (node (ref "V1") (pin "2") (pinfunction "Vout_2") (pintype "passive"))
      (node (ref "V1") (pin "4") (pinfunction "OUT_4") (pintype "passive"))
    )
    (net (code "46") (name "VCC_5V") (class "Default")
      (node (ref "C2") (pin "1") (pinfunction "A_1") (pintype "passive"))
      (node (ref "C4") (pin "2") (pinfunction "2_2") (pintype "passive"))
      (node (ref "D2") (pin "2") (pinfunction "K_2") (pintype "passive"))
      (node (ref "E1") (pin "1") (pinfunction "1_1") (pintype "passive"))
      (node (ref "JP4") (pin "1") (pinfunction "1_1") (pintype "passive"))
      (node (ref "LS1") (pin "1") (pinfunction "1_1") (pintype "passive"))
      (node (ref "V1") (pin "3") (pinfunction "Vin_3") (pintype "passive"))
    )
    (net (code "47") (name "unconnected-(OSC1-Tri-state-Pad1)") (class "Default")
      (node (ref "OSC1") (pin "1") (pinfunction "Tri-state_1") (pintype "passive"))
    )
    (net (code "48") (name "unconnected-(TypeC1-CC1-Pad3)") (class "Default")
      (node (ref "TypeC1") (pin "3") (pinfunction "CC1_3") (pintype "passive"))
    )
    (net (code "49") (name "unconnected-(TypeC1-CC2-Pad10)") (class "Default")
      (node (ref "TypeC1") (pin "10") (pinfunction "CC2_10") (pintype "passive"))
    )
    (net (code "50") (name "unconnected-(TypeC1-VBUS-Pad2)") (class "Default")
      (node (ref "TypeC1") (pin "2") (pinfunction "VBUS_2") (pintype "passive"))
    )
    (net (code "51") (name "unconnected-(TypeC1-VBUS-Pad6)") (class "Default")
      (node (ref "TypeC1") (pin "6") (pinfunction "VBUS_6") (pintype "passive"))
    )
    (net (code "52") (name "unconnected-(TypeC1-VBUS-Pad9)") (class "Default")
      (node (ref "TypeC1") (pin "9") (pinfunction "VBUS_9") (pintype "passive"))
    )
    (net (code "53") (name "unconnected-(TypeC1-VBUS-Pad13)") (class "Default")
      (node (ref "TypeC1") (pin "13") (pinfunction "VBUS_13") (pintype "passive"))
    )
    (net (code "54") (name "unconnected-(U1-PA6-Pad30)") (class "Default")
      (node (ref "U1") (pin "30") (pinfunction "PA6_30") (pintype "passive"))
    )
    (net (code "55") (name "unconnected-(U1-PA7-Pad31)") (class "Default")
      (node (ref "U1") (pin "31") (pinfunction "PA7_31") (pintype "passive"))
    )
    (net (code "56") (name "unconnected-(U1-PA8-Pad67)") (class "Default")
      (node (ref "U1") (pin "67") (pinfunction "PA8_67") (pintype "passive"))
    )
    (net (code "57") (name "unconnected-(U1-PA9-Pad68)") (class "Default")
      (node (ref "U1") (pin "68") (pinfunction "PA9_68") (pintype "passive"))
    )
    (net (code "58") (name "unconnected-(U1-PA10-Pad69)") (class "Default")
      (node (ref "U1") (pin "69") (pinfunction "PA10_69") (pintype "passive"))
    )
    (net (code "59") (name "unconnected-(U1-PB0-Pad34)") (class "Default")
      (node (ref "U1") (pin "34") (pinfunction "PB0_34") (pintype "passive"))
    )
    (net (code "60") (name "unconnected-(U1-PB1-Pad35)") (class "Default")
      (node (ref "U1") (pin "35") (pinfunction "PB1_35") (pintype "passive"))
    )
    (net (code "61") (name "unconnected-(U1-PB3-Pad89)") (class "Default")
      (node (ref "U1") (pin "89") (pinfunction "PB3_89") (pintype "passive"))
    )
    (net (code "62") (name "unconnected-(U1-PB4-Pad90)") (class "Default")
      (node (ref "U1") (pin "90") (pinfunction "PB4_90") (pintype "passive"))
    )
    (net (code "63") (name "unconnected-(U1-PB5-Pad91)") (class "Default")
      (node (ref "U1") (pin "91") (pinfunction "PB5_91") (pintype "passive"))
    )
    (net (code "64") (name "unconnected-(U1-PB6-Pad92)") (class "Default")
      (node (ref "U1") (pin "92") (pinfunction "PB6_92") (pintype "passive"))
    )
    (net (code "65") (name "unconnected-(U1-PB7-Pad93)") (class "Default")
      (node (ref "U1") (pin "93") (pinfunction "PB7_93") (pintype "passive"))
    )
    (net (code "66") (name "unconnected-(U1-PB8-Pad95)") (class "Default")
      (node (ref "U1") (pin "95") (pinfunction "PB8_95") (pintype "passive"))
    )
    (net (code "67") (name "unconnected-(U1-PB14-Pad53)") (class "Default")
      (node (ref "U1") (pin "53") (pinfunction "PB14_53") (pintype "passive"))
    )
    (net (code "68") (name "unconnected-(U1-PB15-Pad54)") (class "Default")
      (node (ref "U1") (pin "54") (pinfunction "PB15_54") (pintype "passive"))
    )
    (net (code "69") (name "unconnected-(U1-PC0-Pad15)") (class "Default")
      (node (ref "U1") (pin "15") (pinfunction "PC0_15") (pintype "passive"))
    )
    (net (code "70") (name "unconnected-(U1-PC1-Pad16)") (class "Default")
      (node (ref "U1") (pin "16") (pinfunction "PC1_16") (pintype "passive"))
    )
    (net (code "71") (name "unconnected-(U1-PC2_C-Pad17)") (class "Default")
      (node (ref "U1") (pin "17") (pinfunction "PC2_C_17") (pintype "passive"))
    )
    (net (code "72") (name "unconnected-(U1-PC3_C-Pad18)") (class "Default")
      (node (ref "U1") (pin "18") (pinfunction "PC3_C_18") (pintype "passive"))
    )
    (net (code "73") (name "unconnected-(U1-PC4-Pad32)") (class "Default")
      (node (ref "U1") (pin "32") (pinfunction "PC4_32") (pintype "passive"))
    )
    (net (code "74") (name "unconnected-(U1-PC5-Pad33)") (class "Default")
      (node (ref "U1") (pin "33") (pinfunction "PC5_33") (pintype "passive"))
    )
    (net (code "75") (name "unconnected-(U1-PC6-Pad63)") (class "Default")
      (node (ref "U1") (pin "63") (pinfunction "PC6_63") (pintype "passive"))
    )
    (net (code "76") (name "unconnected-(U1-PC7-Pad64)") (class "Default")
      (node (ref "U1") (pin "64") (pinfunction "PC7_64") (pintype "passive"))
    )
    (net (code "77") (name "unconnected-(U1-PC9-Pad66)") (class "Default")
      (node (ref "U1") (pin "66") (pinfunction "PC9_66") (pintype "passive"))
    )
    (net (code "78") (name "unconnected-(U1-PC10-Pad78)") (class "Default")
      (node (ref "U1") (pin "78") (pinfunction "PC10_78") (pintype "passive"))
    )
    (net (code "79") (name "unconnected-(U1-PC12-Pad80)") (class "Default")
      (node (ref "U1") (pin "80") (pinfunction "PC12_80") (pintype "passive"))
    )
    (net (code "80") (name "unconnected-(U1-PC13-Pad7)") (class "Default")
      (node (ref "U1") (pin "7") (pinfunction "PC13_7") (pintype "passive"))
    )
    (net (code "81") (name "unconnected-(U1-PC14-OSC32_IN-Pad8)") (class "Default")
      (node (ref "U1") (pin "8") (pinfunction "PC14-OSC32_IN_8") (pintype "passive"))
    )
    (net (code "82") (name "unconnected-(U1-PC15-OSC32_OUT-Pad9)") (class "Default")
      (node (ref "U1") (pin "9") (pinfunction "PC15-OSC32_OUT_9") (pintype "passive"))
    )
    (net (code "83") (name "unconnected-(U1-PD0-Pad81)") (class "Default")
      (node (ref "U1") (pin "81") (pinfunction "PD0_81") (pintype "passive"))
    )
    (net (code "84") (name "unconnected-(U1-PD1-Pad82)") (class "Default")
      (node (ref "U1") (pin "82") (pinfunction "PD1_82") (pintype "passive"))
    )
    (net (code "85") (name "unconnected-(U1-PD2-Pad83)") (class "Default")
      (node (ref "U1") (pin "83") (pinfunction "PD2_83") (pintype "passive"))
    )
    (net (code "86") (name "unconnected-(U1-PD3-Pad84)") (class "Default")
      (node (ref "U1") (pin "84") (pinfunction "PD3_84") (pintype "passive"))
    )
    (net (code "87") (name "unconnected-(U1-PD4-Pad85)") (class "Default")
      (node (ref "U1") (pin "85") (pinfunction "PD4_85") (pintype "passive"))
    )
    (net (code "88") (name "unconnected-(U1-PD5-Pad86)") (class "Default")
      (node (ref "U1") (pin "86") (pinfunction "PD5_86") (pintype "passive"))
    )
    (net (code "89") (name "unconnected-(U1-PD6-Pad87)") (class "Default")
      (node (ref "U1") (pin "87") (pinfunction "PD6_87") (pintype "passive"))
    )
    (net (code "90") (name "unconnected-(U1-PD7-Pad88)") (class "Default")
      (node (ref "U1") (pin "88") (pinfunction "PD7_88") (pintype "passive"))
    )
    (net (code "91") (name "unconnected-(U1-PD8-Pad55)") (class "Default")
      (node (ref "U1") (pin "55") (pinfunction "PD8_55") (pintype "passive"))
    )
    (net (code "92") (name "unconnected-(U1-PD9-Pad56)") (class "Default")
      (node (ref "U1") (pin "56") (pinfunction "PD9_56") (pintype "passive"))
    )
    (net (code "93") (name "unconnected-(U1-PD10-Pad57)") (class "Default")
      (node (ref "U1") (pin "57") (pinfunction "PD10_57") (pintype "passive"))
    )
    (net (code "94") (name "unconnected-(U1-PD11-Pad58)") (class "Default")
      (node (ref "U1") (pin "58") (pinfunction "PD11_58") (pintype "passive"))
    )
    (net (code "95") (name "unconnected-(U1-PD13-Pad60)") (class "Default")
      (node (ref "U1") (pin "60") (pinfunction "PD13_60") (pintype "passive"))
    )
    (net (code "96") (name "unconnected-(U1-PD14-Pad61)") (class "Default")
      (node (ref "U1") (pin "61") (pinfunction "PD14_61") (pintype "passive"))
    )
    (net (code "97") (name "unconnected-(U1-PD15-Pad62)") (class "Default")
      (node (ref "U1") (pin "62") (pinfunction "PD15_62") (pintype "passive"))
    )
    (net (code "98") (name "unconnected-(U1-PE0-Pad97)") (class "Default")
      (node (ref "U1") (pin "97") (pinfunction "PE0_97") (pintype "passive"))
    )
    (net (code "99") (name "unconnected-(U1-PE1-Pad98)") (class "Default")
      (node (ref "U1") (pin "98") (pinfunction "PE1_98") (pintype "passive"))
    )
    (net (code "100") (name "unconnected-(U1-PE2-Pad1)") (class "Default")
      (node (ref "U1") (pin "1") (pinfunction "PE2_1") (pintype "passive"))
    )
    (net (code "101") (name "unconnected-(U1-PE3-Pad2)") (class "Default")
      (node (ref "U1") (pin "2") (pinfunction "PE3_2") (pintype "passive"))
    )
    (net (code "102") (name "unconnected-(U1-PE4-Pad3)") (class "Default")
      (node (ref "U1") (pin "3") (pinfunction "PE4_3") (pintype "passive"))
    )
    (net (code "103") (name "unconnected-(U1-PE5-Pad4)") (class "Default")
      (node (ref "U1") (pin "4") (pinfunction "PE5_4") (pintype "passive"))
    )
    (net (code "104") (name "unconnected-(U1-PE6-Pad5)") (class "Default")
      (node (ref "U1") (pin "5") (pinfunction "PE6_5") (pintype "passive"))
    )
    (net (code "105") (name "unconnected-(U1-PE7-Pad37)") (class "Default")
      (node (ref "U1") (pin "37") (pinfunction "PE7_37") (pintype "passive"))
    )
    (net (code "106") (name "unconnected-(U1-PE8-Pad38)") (class "Default")
      (node (ref "U1") (pin "38") (pinfunction "PE8_38") (pintype "passive"))
    )
    (net (code "107") (name "unconnected-(U1-PE9-Pad39)") (class "Default")
      (node (ref "U1") (pin "39") (pinfunction "PE9_39") (pintype "passive"))
    )
    (net (code "108") (name "unconnected-(U1-PE10-Pad40)") (class "Default")
      (node (ref "U1") (pin "40") (pinfunction "PE10_40") (pintype "passive"))
    )
    (net (code "109") (name "unconnected-(U1-PE11-Pad41)") (class "Default")
      (node (ref "U1") (pin "41") (pinfunction "PE11_41") (pintype "passive"))
    )
    (net (code "110") (name "unconnected-(U1-PE12-Pad42)") (class "Default")
      (node (ref "U1") (pin "42") (pinfunction "PE12_42") (pintype "passive"))
    )
    (net (code "111") (name "unconnected-(U1-PE13-Pad43)") (class "Default")
      (node (ref "U1") (pin "43") (pinfunction "PE13_43") (pintype "passive"))
    )
    (net (code "112") (name "unconnected-(U1-PE14-Pad44)") (class "Default")
      (node (ref "U1") (pin "44") (pinfunction "PE14_44") (pintype "passive"))
    )
    (net (code "113") (name "unconnected-(U1-PE15-Pad45)") (class "Default")
      (node (ref "U1") (pin "45") (pinfunction "PE15_45") (pintype "passive"))
    )
    (net (code "114") (name "unconnected-(U1-PH1-OSC_OUT-Pad13)") (class "Default")
      (node (ref "U1") (pin "13") (pinfunction "PH1-OSC_OUT_13") (pintype "passive"))
    )
  )
)
